# Lighting_Schematic.net
KiCad netlist of a schematic drawn in EAGLE
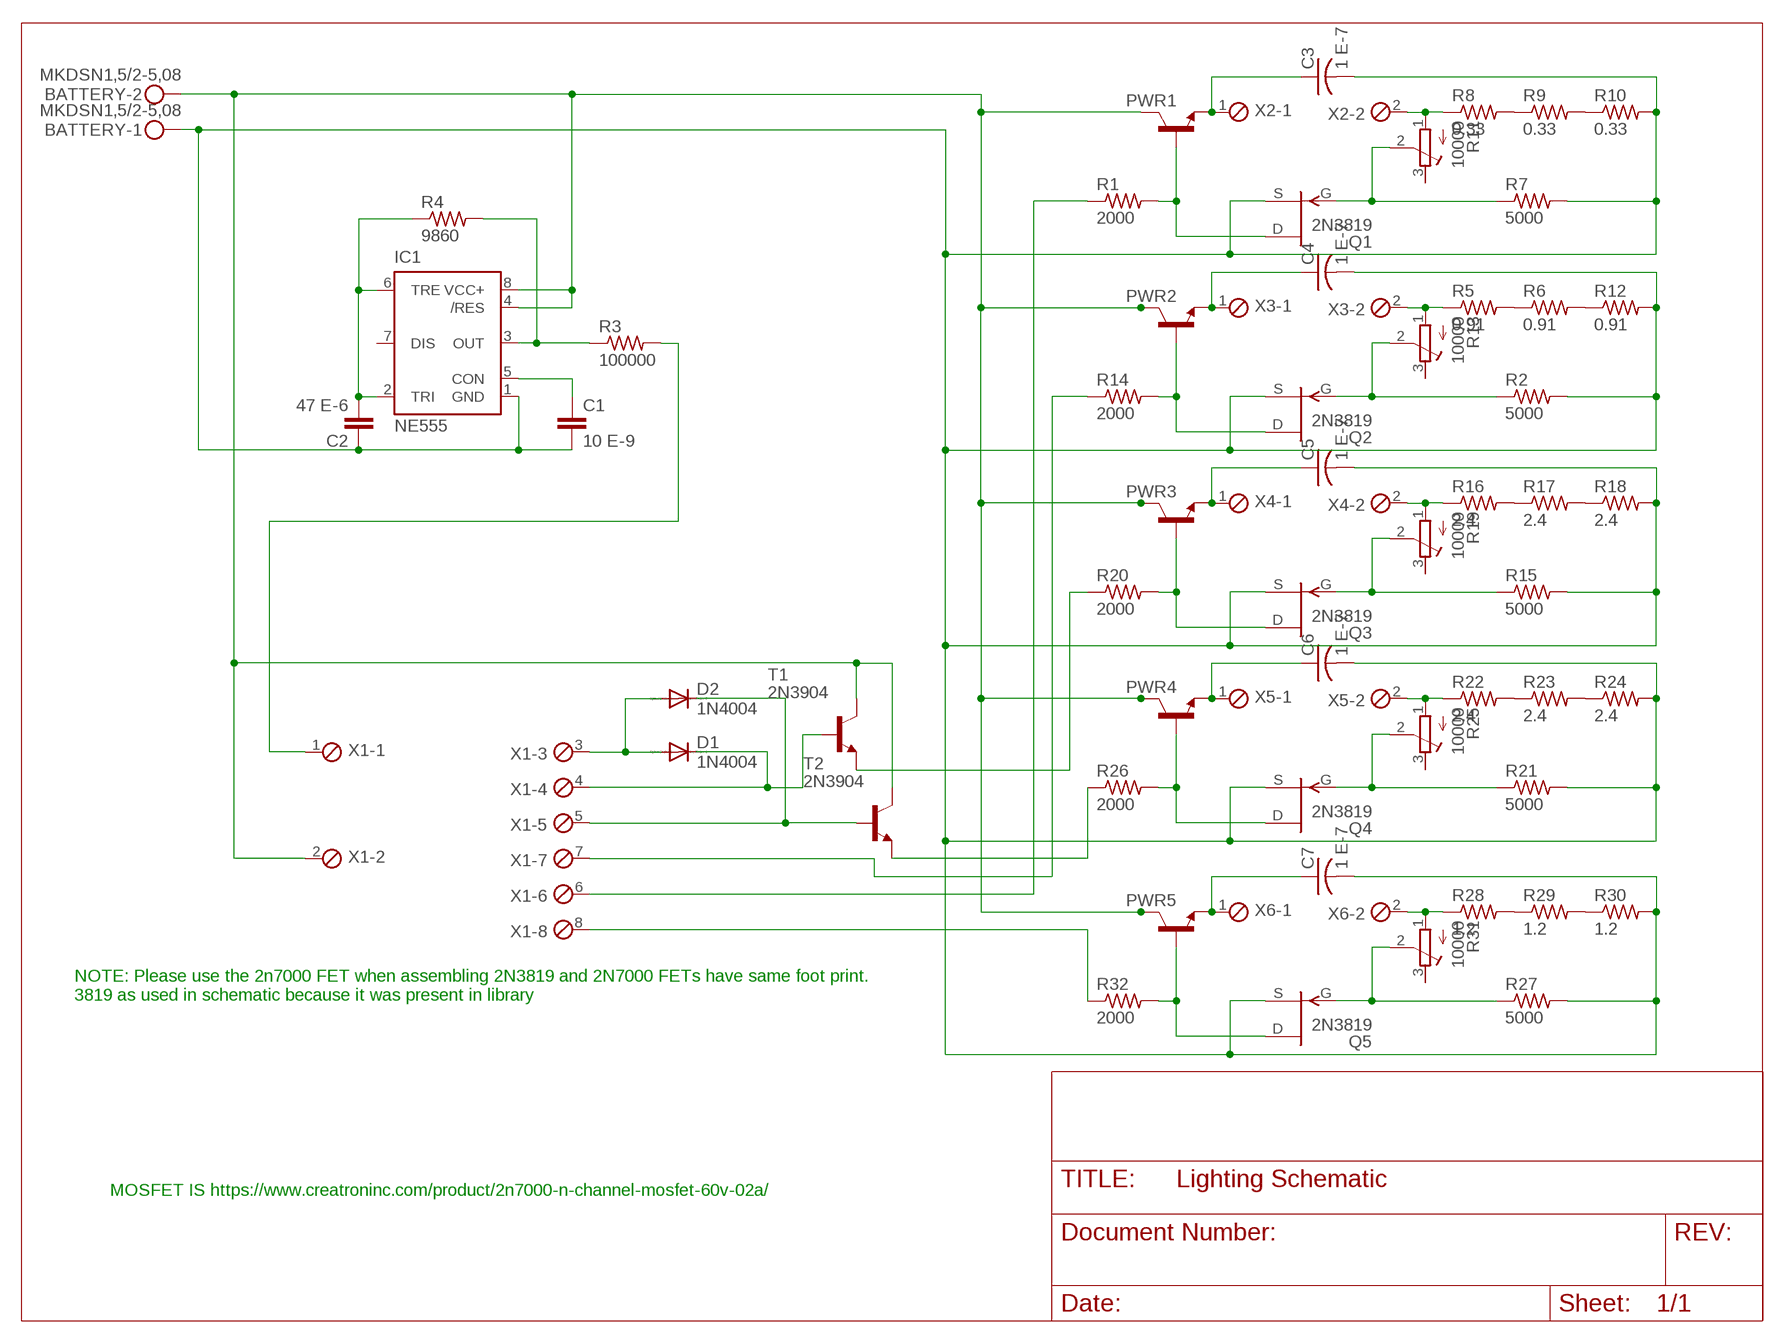
[diagram p0: schematic, sheet 1]

(export (version "E")
  (design (tool "Eeschema 10.0.6"))
  (components
    (comp (ref "BATTERY")
      (value "MKDSN1,5/2-5,08")
      (footprint "eagle-import:MKDSN1,5_2-5,08")
      (libsource (lib "eagle-import") (part "MKDSN1,5/2-5,08"))
    )
    (comp (ref "C1")
      (value "10 E-9")
      (footprint "eagle-import:C2.5-5")
      (libsource (lib "eagle-import") (part "C2.5/5"))
    )
    (comp (ref "C2")
      (value "47 E-6")
      (footprint "eagle-import:C2.5-5")
      (libsource (lib "eagle-import") (part "C2.5/5"))
    )
    (comp (ref "C3")
      (value "1 E-7")
      (footprint "eagle-import:C075-052X106")
      (libsource (lib "eagle-import") (part "C-US075-052X106"))
    )
    (comp (ref "C4")
      (value "1 E-7")
      (footprint "eagle-import:C075-052X106")
      (libsource (lib "eagle-import") (part "C-US075-052X106"))
    )
    (comp (ref "C5")
      (value "1 E-7")
      (footprint "eagle-import:C075-052X106")
      (libsource (lib "eagle-import") (part "C-US075-052X106"))
    )
    (comp (ref "C6")
      (value "1 E-7")
      (footprint "eagle-import:C075-052X106")
      (libsource (lib "eagle-import") (part "C-US075-052X106"))
    )
    (comp (ref "C7")
      (value "1 E-7")
      (footprint "eagle-import:C075-052X106")
      (libsource (lib "eagle-import") (part "C-US075-052X106"))
    )
    (comp (ref "D1")
      (value "1N4004")
      (footprint "eagle-import:DO41-10")
      (libsource (lib "eagle-import") (part "1N4004"))
    )
    (comp (ref "D2")
      (value "1N4004")
      (footprint "eagle-import:DO41-10")
      (libsource (lib "eagle-import") (part "1N4004"))
    )
    (comp (ref "IC1")
      (value "NE555")
      (footprint "eagle-import:DIL-08")
      (fields (field (name "MF") "Arrow Electronics") (field (name "MPN") "NE555N"))
      (libsource (lib "eagle-import") (part "NE555"))
    )
    (comp (ref "PWR1")
      (value "-NPN-TO220V")
      (footprint "eagle-import:TO220V")
      (libsource (lib "eagle-import") (part "-NPN-TO220V"))
    )
    (comp (ref "PWR2")
      (value "-NPN-TO220V")
      (footprint "eagle-import:TO220V")
      (libsource (lib "eagle-import") (part "-NPN-TO220V"))
    )
    (comp (ref "PWR3")
      (value "-NPN-TO220V")
      (footprint "eagle-import:TO220V")
      (libsource (lib "eagle-import") (part "-NPN-TO220V"))
    )
    (comp (ref "PWR4")
      (value "-NPN-TO220V")
      (footprint "eagle-import:TO220V")
      (libsource (lib "eagle-import") (part "-NPN-TO220V"))
    )
    (comp (ref "PWR5")
      (value "-NPN-TO220V")
      (footprint "eagle-import:TO220V")
      (libsource (lib "eagle-import") (part "-NPN-TO220V"))
    )
    (comp (ref "Q1")
      (value "2N3819")
      (footprint "eagle-import:TO92")
      (libsource (lib "eagle-import") (part "2N3819"))
    )
    (comp (ref "Q2")
      (value "2N3819")
      (footprint "eagle-import:TO92")
      (libsource (lib "eagle-import") (part "2N3819"))
    )
    (comp (ref "Q3")
      (value "2N3819")
      (footprint "eagle-import:TO92")
      (libsource (lib "eagle-import") (part "2N3819"))
    )
    (comp (ref "Q4")
      (value "2N3819")
      (footprint "eagle-import:TO92")
      (libsource (lib "eagle-import") (part "2N3819"))
    )
    (comp (ref "Q5")
      (value "2N3819")
      (footprint "eagle-import:TO92")
      (libsource (lib "eagle-import") (part "2N3819"))
    )
    (comp (ref "R1")
      (value "2000")
      (footprint "eagle-import:0207_15")
      (libsource (lib "eagle-import") (part "resistor_348_R-US_0207/15"))
    )
    (comp (ref "R2")
      (value "5000")
      (footprint "eagle-import:0207_10")
      (libsource (lib "eagle-import") (part "R-US_0207/10"))
    )
    (comp (ref "R3")
      (value "100000")
      (footprint "eagle-import:0207_10")
      (libsource (lib "eagle-import") (part "R-US_0207/10"))
    )
    (comp (ref "R4")
      (value "9860")
      (footprint "eagle-import:0207_10")
      (libsource (lib "eagle-import") (part "R-US_0207/10"))
    )
    (comp (ref "R5")
      (value "0.91")
      (footprint "eagle-import:P0817V")
      (libsource (lib "eagle-import") (part "R-US_0817/7V"))
    )
    (comp (ref "R6")
      (value "0.91")
      (footprint "eagle-import:P0817V")
      (libsource (lib "eagle-import") (part "R-US_0817/7V"))
    )
    (comp (ref "R7")
      (value "5000")
      (footprint "eagle-import:0207_10")
      (libsource (lib "eagle-import") (part "R-US_0207/10"))
    )
    (comp (ref "R8")
      (value "0.33")
      (footprint "eagle-import:P0817V")
      (libsource (lib "eagle-import") (part "R-US_0817/7V"))
    )
    (comp (ref "R9")
      (value "0.33")
      (footprint "eagle-import:P0817V")
      (libsource (lib "eagle-import") (part "R-US_0817/7V"))
    )
    (comp (ref "R10")
      (value "0.33")
      (footprint "eagle-import:P0817V")
      (libsource (lib "eagle-import") (part "R-US_0817/7V"))
    )
    (comp (ref "R11")
      (value "10000")
      (footprint "eagle-import:RTRIM3296W")
      (libsource (lib "eagle-import") (part "R-TRIMM3296W"))
    )
    (comp (ref "R12")
      (value "0.91")
      (footprint "eagle-import:P0817V")
      (libsource (lib "eagle-import") (part "R-US_0817/7V"))
    )
    (comp (ref "R13")
      (value "10000")
      (footprint "eagle-import:RTRIM3296W")
      (libsource (lib "eagle-import") (part "R-TRIMM3296W"))
    )
    (comp (ref "R14")
      (value "2000")
      (footprint "eagle-import:0207_15")
      (libsource (lib "eagle-import") (part "resistor_348_R-US_0207/15"))
    )
    (comp (ref "R15")
      (value "5000")
      (footprint "eagle-import:0207_10")
      (libsource (lib "eagle-import") (part "R-US_0207/10"))
    )
    (comp (ref "R16")
      (value "2.4")
      (footprint "eagle-import:P0817V")
      (libsource (lib "eagle-import") (part "R-US_0817/7V"))
    )
    (comp (ref "R17")
      (value "2.4")
      (footprint "eagle-import:P0817V")
      (libsource (lib "eagle-import") (part "R-US_0817/7V"))
    )
    (comp (ref "R18")
      (value "2.4")
      (footprint "eagle-import:P0817V")
      (libsource (lib "eagle-import") (part "R-US_0817/7V"))
    )
    (comp (ref "R19")
      (value "10000")
      (footprint "eagle-import:RTRIM3296W")
      (libsource (lib "eagle-import") (part "R-TRIMM3296W"))
    )
    (comp (ref "R20")
      (value "2000")
      (footprint "eagle-import:0207_15")
      (libsource (lib "eagle-import") (part "resistor_348_R-US_0207/15"))
    )
    (comp (ref "R21")
      (value "5000")
      (footprint "eagle-import:0207_10")
      (libsource (lib "eagle-import") (part "R-US_0207/10"))
    )
    (comp (ref "R22")
      (value "2.4")
      (footprint "eagle-import:P0817V")
      (libsource (lib "eagle-import") (part "R-US_0817/7V"))
    )
    (comp (ref "R23")
      (value "2.4")
      (footprint "eagle-import:P0817V")
      (libsource (lib "eagle-import") (part "R-US_0817/7V"))
    )
    (comp (ref "R24")
      (value "2.4")
      (footprint "eagle-import:P0817V")
      (libsource (lib "eagle-import") (part "R-US_0817/7V"))
    )
    (comp (ref "R25")
      (value "10000")
      (footprint "eagle-import:RTRIM3296W")
      (libsource (lib "eagle-import") (part "R-TRIMM3296W"))
    )
    (comp (ref "R26")
      (value "2000")
      (footprint "eagle-import:0207_15")
      (libsource (lib "eagle-import") (part "resistor_348_R-US_0207/15"))
    )
    (comp (ref "R27")
      (value "5000")
      (footprint "eagle-import:0207_10")
      (libsource (lib "eagle-import") (part "R-US_0207/10"))
    )
    (comp (ref "R28")
      (value "1.2")
      (footprint "eagle-import:P0817V")
      (libsource (lib "eagle-import") (part "R-US_0817/7V"))
    )
    (comp (ref "R29")
      (value "1.2")
      (footprint "eagle-import:P0817V")
      (libsource (lib "eagle-import") (part "R-US_0817/7V"))
    )
    (comp (ref "R30")
      (value "1.2")
      (footprint "eagle-import:P0817V")
      (libsource (lib "eagle-import") (part "R-US_0817/7V"))
    )
    (comp (ref "R31")
      (value "10000")
      (footprint "eagle-import:RTRIM3296W")
      (libsource (lib "eagle-import") (part "R-TRIMM3296W"))
    )
    (comp (ref "R32")
      (value "2000")
      (footprint "eagle-import:0207_15")
      (libsource (lib "eagle-import") (part "resistor_348_R-US_0207/15"))
    )
    (comp (ref "T1")
      (value "2N3904")
      (footprint "eagle-import:TO92")
      (libsource (lib "eagle-import") (part "2N3904"))
    )
    (comp (ref "T2")
      (value "2N3904")
      (footprint "eagle-import:TO92")
      (libsource (lib "eagle-import") (part "2N3904"))
    )
    (comp (ref "X1")
      (value "MPT8")
      (footprint "eagle-import:8POL254")
      (libsource (lib "eagle-import") (part "MPT8"))
    )
    (comp (ref "X2")
      (value "MPT2")
      (footprint "eagle-import:2POL254")
      (libsource (lib "eagle-import") (part "MPT2"))
    )
    (comp (ref "X3")
      (value "MPT2")
      (footprint "eagle-import:2POL254")
      (libsource (lib "eagle-import") (part "MPT2"))
    )
    (comp (ref "X4")
      (value "MPT2")
      (footprint "eagle-import:2POL254")
      (libsource (lib "eagle-import") (part "MPT2"))
    )
    (comp (ref "X5")
      (value "MPT2")
      (footprint "eagle-import:2POL254")
      (libsource (lib "eagle-import") (part "MPT2"))
    )
    (comp (ref "X6")
      (value "MPT2")
      (footprint "eagle-import:2POL254")
      (libsource (lib "eagle-import") (part "MPT2"))
    )
  )
  (nets
    (net (code "1") (name "Net-(BATTERYA-KL)") (class "Default")
      (node (ref "BATTERY") (pin "1") (pinfunction "KL_1") (pintype "passive"))
      (node (ref "C1") (pin "2") (pinfunction "2_2") (pintype "passive"))
      (node (ref "C2") (pin "1") (pinfunction "1_1") (pintype "passive"))
      (node (ref "C3") (pin "2") (pinfunction "2_2") (pintype "passive"))
      (node (ref "C4") (pin "2") (pinfunction "2_2") (pintype "passive"))
      (node (ref "C5") (pin "2") (pinfunction "2_2") (pintype "passive"))
      (node (ref "C6") (pin "2") (pinfunction "2_2") (pintype "passive"))
      (node (ref "C7") (pin "2") (pinfunction "2_2") (pintype "passive"))
      (node (ref "IC1") (pin "1") (pinfunction "GND_1") (pintype "power_in"))
      (node (ref "Q1") (pin "3") (pinfunction "S_3") (pintype "passive"))
      (node (ref "Q2") (pin "3") (pinfunction "S_3") (pintype "passive"))
      (node (ref "Q3") (pin "3") (pinfunction "S_3") (pintype "passive"))
      (node (ref "Q4") (pin "3") (pinfunction "S_3") (pintype "passive"))
      (node (ref "Q5") (pin "3") (pinfunction "S_3") (pintype "passive"))
      (node (ref "R10") (pin "2") (pinfunction "2_2") (pintype "passive"))
      (node (ref "R12") (pin "2") (pinfunction "2_2") (pintype "passive"))
      (node (ref "R15") (pin "2") (pinfunction "2_2") (pintype "passive"))
      (node (ref "R18") (pin "2") (pinfunction "2_2") (pintype "passive"))
      (node (ref "R2") (pin "2") (pinfunction "2_2") (pintype "passive"))
      (node (ref "R21") (pin "2") (pinfunction "2_2") (pintype "passive"))
      (node (ref "R24") (pin "2") (pinfunction "2_2") (pintype "passive"))
      (node (ref "R27") (pin "2") (pinfunction "2_2") (pintype "passive"))
      (node (ref "R30") (pin "2") (pinfunction "2_2") (pintype "passive"))
      (node (ref "R7") (pin "2") (pinfunction "2_2") (pintype "passive"))
    )
    (net (code "2") (name "Net-(BATTERYB-KL)") (class "Default")
      (node (ref "BATTERY") (pin "2") (pinfunction "KL_2") (pintype "passive"))
      (node (ref "IC1") (pin "4") (pinfunction "/RES_4") (pintype "input"))
      (node (ref "IC1") (pin "8") (pinfunction "VCC+_8") (pintype "power_in"))
      (node (ref "PWR1") (pin "2") (pinfunction "C_2") (pintype "passive"))
      (node (ref "PWR2") (pin "2") (pinfunction "C_2") (pintype "passive"))
      (node (ref "PWR3") (pin "2") (pinfunction "C_2") (pintype "passive"))
      (node (ref "PWR4") (pin "2") (pinfunction "C_2") (pintype "passive"))
      (node (ref "PWR5") (pin "2") (pinfunction "C_2") (pintype "passive"))
      (node (ref "T1") (pin "1") (pinfunction "C_1") (pintype "passive"))
      (node (ref "T2") (pin "1") (pinfunction "C_1") (pintype "passive"))
      (node (ref "X1") (pin "2") (pinfunction "1_2") (pintype "passive"))
    )
    (net (code "3") (name "Net-(IC1-CON)") (class "Default")
      (node (ref "C1") (pin "1") (pinfunction "1_1") (pintype "passive"))
      (node (ref "IC1") (pin "5") (pinfunction "CON_5") (pintype "input"))
    )
    (net (code "4") (name "Net-(IC1-OUT)") (class "Default")
      (node (ref "IC1") (pin "3") (pinfunction "OUT_3") (pintype "output"))
      (node (ref "R3") (pin "1") (pinfunction "1_1") (pintype "passive"))
      (node (ref "R4") (pin "2") (pinfunction "2_2") (pintype "passive"))
    )
    (net (code "5") (name "Net-(IC1-TRE)") (class "Default")
      (node (ref "C2") (pin "2") (pinfunction "2_2") (pintype "passive"))
      (node (ref "IC1") (pin "2") (pinfunction "TRI_2") (pintype "input"))
      (node (ref "IC1") (pin "6") (pinfunction "TRE_6") (pintype "input"))
      (node (ref "R4") (pin "1") (pinfunction "1_1") (pintype "passive"))
    )
    (net (code "6") (name "Net-(PWR1-B)") (class "Default")
      (node (ref "PWR1") (pin "1") (pinfunction "B_1") (pintype "passive"))
      (node (ref "Q1") (pin "1") (pinfunction "D_1") (pintype "passive"))
      (node (ref "R1") (pin "2") (pinfunction "2_2") (pintype "passive"))
    )
    (net (code "7") (name "Net-(PWR1-E)") (class "Default")
      (node (ref "C3") (pin "1") (pinfunction "1_1") (pintype "passive"))
      (node (ref "PWR1") (pin "3") (pinfunction "E_3") (pintype "passive"))
      (node (ref "X2") (pin "1") (pinfunction "1_1") (pintype "passive"))
    )
    (net (code "8") (name "Net-(PWR2-B)") (class "Default")
      (node (ref "PWR2") (pin "1") (pinfunction "B_1") (pintype "passive"))
      (node (ref "Q2") (pin "1") (pinfunction "D_1") (pintype "passive"))
      (node (ref "R14") (pin "2") (pinfunction "2_2") (pintype "passive"))
    )
    (net (code "9") (name "Net-(PWR2-E)") (class "Default")
      (node (ref "C4") (pin "1") (pinfunction "1_1") (pintype "passive"))
      (node (ref "PWR2") (pin "3") (pinfunction "E_3") (pintype "passive"))
      (node (ref "X3") (pin "1") (pinfunction "1_1") (pintype "passive"))
    )
    (net (code "10") (name "Net-(PWR3-B)") (class "Default")
      (node (ref "PWR3") (pin "1") (pinfunction "B_1") (pintype "passive"))
      (node (ref "Q3") (pin "1") (pinfunction "D_1") (pintype "passive"))
      (node (ref "R20") (pin "2") (pinfunction "2_2") (pintype "passive"))
    )
    (net (code "11") (name "Net-(PWR3-E)") (class "Default")
      (node (ref "C5") (pin "1") (pinfunction "1_1") (pintype "passive"))
      (node (ref "PWR3") (pin "3") (pinfunction "E_3") (pintype "passive"))
      (node (ref "X4") (pin "1") (pinfunction "1_1") (pintype "passive"))
    )
    (net (code "12") (name "Net-(PWR4-B)") (class "Default")
      (node (ref "PWR4") (pin "1") (pinfunction "B_1") (pintype "passive"))
      (node (ref "Q4") (pin "1") (pinfunction "D_1") (pintype "passive"))
      (node (ref "R26") (pin "2") (pinfunction "2_2") (pintype "passive"))
    )
    (net (code "13") (name "Net-(PWR4-E)") (class "Default")
      (node (ref "C6") (pin "1") (pinfunction "1_1") (pintype "passive"))
      (node (ref "PWR4") (pin "3") (pinfunction "E_3") (pintype "passive"))
      (node (ref "X5") (pin "1") (pinfunction "1_1") (pintype "passive"))
    )
    (net (code "14") (name "Net-(PWR5-B)") (class "Default")
      (node (ref "PWR5") (pin "1") (pinfunction "B_1") (pintype "passive"))
      (node (ref "Q5") (pin "1") (pinfunction "D_1") (pintype "passive"))
      (node (ref "R32") (pin "2") (pinfunction "2_2") (pintype "passive"))
    )
    (net (code "15") (name "Net-(PWR5-E)") (class "Default")
      (node (ref "C7") (pin "1") (pinfunction "1_1") (pintype "passive"))
      (node (ref "PWR5") (pin "3") (pinfunction "E_3") (pintype "passive"))
      (node (ref "X6") (pin "1") (pinfunction "1_1") (pintype "passive"))
    )
    (net (code "16") (name "Net-(Q1-G)") (class "Default")
      (node (ref "Q1") (pin "2") (pinfunction "G_2") (pintype "passive"))
      (node (ref "R11") (pin "2") (pinfunction "S_2") (pintype "passive"))
      (node (ref "R7") (pin "1") (pinfunction "1_1") (pintype "passive"))
    )
    (net (code "17") (name "Net-(Q2-G)") (class "Default")
      (node (ref "Q2") (pin "2") (pinfunction "G_2") (pintype "passive"))
      (node (ref "R13") (pin "2") (pinfunction "S_2") (pintype "passive"))
      (node (ref "R2") (pin "1") (pinfunction "1_1") (pintype "passive"))
    )
    (net (code "18") (name "Net-(Q3-G)") (class "Default")
      (node (ref "Q3") (pin "2") (pinfunction "G_2") (pintype "passive"))
      (node (ref "R15") (pin "1") (pinfunction "1_1") (pintype "passive"))
      (node (ref "R19") (pin "2") (pinfunction "S_2") (pintype "passive"))
    )
    (net (code "19") (name "Net-(Q4-G)") (class "Default")
      (node (ref "Q4") (pin "2") (pinfunction "G_2") (pintype "passive"))
      (node (ref "R21") (pin "1") (pinfunction "1_1") (pintype "passive"))
      (node (ref "R25") (pin "2") (pinfunction "S_2") (pintype "passive"))
    )
    (net (code "20") (name "Net-(Q5-G)") (class "Default")
      (node (ref "Q5") (pin "2") (pinfunction "G_2") (pintype "passive"))
      (node (ref "R27") (pin "1") (pinfunction "1_1") (pintype "passive"))
      (node (ref "R31") (pin "2") (pinfunction "S_2") (pintype "passive"))
    )
    (net (code "21") (name "Net-(R3-Pad2)") (class "Default")
      (node (ref "R3") (pin "2") (pinfunction "2_2") (pintype "passive"))
      (node (ref "X1") (pin "1") (pinfunction "1_1") (pintype "passive"))
    )
    (net (code "22") (name "Net-(R5-Pad2)") (class "Default")
      (node (ref "R5") (pin "2") (pinfunction "2_2") (pintype "passive"))
      (node (ref "R6") (pin "1") (pinfunction "1_1") (pintype "passive"))
    )
    (net (code "23") (name "Net-(R8-Pad2)") (class "Default")
      (node (ref "R8") (pin "2") (pinfunction "2_2") (pintype "passive"))
      (node (ref "R9") (pin "1") (pinfunction "1_1") (pintype "passive"))
    )
    (net (code "24") (name "Net-(R10-Pad1)") (class "Default")
      (node (ref "R10") (pin "1") (pinfunction "1_1") (pintype "passive"))
      (node (ref "R9") (pin "2") (pinfunction "2_2") (pintype "passive"))
    )
    (net (code "25") (name "Net-(R11-A)") (class "Default")
      (node (ref "R11") (pin "1") (pinfunction "A_1") (pintype "passive"))
      (node (ref "R8") (pin "1") (pinfunction "1_1") (pintype "passive"))
      (node (ref "X2") (pin "2") (pinfunction "1_2") (pintype "passive"))
    )
    (net (code "26") (name "Net-(R12-Pad1)") (class "Default")
      (node (ref "R12") (pin "1") (pinfunction "1_1") (pintype "passive"))
      (node (ref "R6") (pin "2") (pinfunction "2_2") (pintype "passive"))
    )
    (net (code "27") (name "Net-(R13-A)") (class "Default")
      (node (ref "R13") (pin "1") (pinfunction "A_1") (pintype "passive"))
      (node (ref "R5") (pin "1") (pinfunction "1_1") (pintype "passive"))
      (node (ref "X3") (pin "2") (pinfunction "1_2") (pintype "passive"))
    )
    (net (code "28") (name "Net-(R16-Pad2)") (class "Default")
      (node (ref "R16") (pin "2") (pinfunction "2_2") (pintype "passive"))
      (node (ref "R17") (pin "1") (pinfunction "1_1") (pintype "passive"))
    )
    (net (code "29") (name "Net-(R17-Pad2)") (class "Default")
      (node (ref "R17") (pin "2") (pinfunction "2_2") (pintype "passive"))
      (node (ref "R18") (pin "1") (pinfunction "1_1") (pintype "passive"))
    )
    (net (code "30") (name "Net-(R19-A)") (class "Default")
      (node (ref "R16") (pin "1") (pinfunction "1_1") (pintype "passive"))
      (node (ref "R19") (pin "1") (pinfunction "A_1") (pintype "passive"))
      (node (ref "X4") (pin "2") (pinfunction "1_2") (pintype "passive"))
    )
    (net (code "31") (name "Net-(R22-Pad2)") (class "Default")
      (node (ref "R22") (pin "2") (pinfunction "2_2") (pintype "passive"))
      (node (ref "R23") (pin "1") (pinfunction "1_1") (pintype "passive"))
    )
    (net (code "32") (name "Net-(R23-Pad2)") (class "Default")
      (node (ref "R23") (pin "2") (pinfunction "2_2") (pintype "passive"))
      (node (ref "R24") (pin "1") (pinfunction "1_1") (pintype "passive"))
    )
    (net (code "33") (name "Net-(R25-A)") (class "Default")
      (node (ref "R22") (pin "1") (pinfunction "1_1") (pintype "passive"))
      (node (ref "R25") (pin "1") (pinfunction "A_1") (pintype "passive"))
      (node (ref "X5") (pin "2") (pinfunction "1_2") (pintype "passive"))
    )
    (net (code "34") (name "Net-(R28-Pad2)") (class "Default")
      (node (ref "R28") (pin "2") (pinfunction "2_2") (pintype "passive"))
      (node (ref "R29") (pin "1") (pinfunction "1_1") (pintype "passive"))
    )
    (net (code "35") (name "Net-(R29-Pad2)") (class "Default")
      (node (ref "R29") (pin "2") (pinfunction "2_2") (pintype "passive"))
      (node (ref "R30") (pin "1") (pinfunction "1_1") (pintype "passive"))
    )
    (net (code "36") (name "Net-(R31-A)") (class "Default")
      (node (ref "R28") (pin "1") (pinfunction "1_1") (pintype "passive"))
      (node (ref "R31") (pin "1") (pinfunction "A_1") (pintype "passive"))
      (node (ref "X6") (pin "2") (pinfunction "1_2") (pintype "passive"))
    )
    (net (code "37") (name "Net-(T1-B)") (class "Default")
      (node (ref "D1") (pin "C") (pinfunction "C_C") (pintype "passive"))
      (node (ref "T1") (pin "2") (pinfunction "B_2") (pintype "passive"))
      (node (ref "X1") (pin "4") (pinfunction "1_4") (pintype "passive"))
    )
    (net (code "38") (name "Net-(T1-E)") (class "Default")
      (node (ref "R20") (pin "1") (pinfunction "1_1") (pintype "passive"))
      (node (ref "T1") (pin "3") (pinfunction "E_3") (pintype "passive"))
    )
    (net (code "39") (name "Net-(T2-B)") (class "Default")
      (node (ref "D2") (pin "C") (pinfunction "C_C") (pintype "passive"))
      (node (ref "T2") (pin "2") (pinfunction "B_2") (pintype "passive"))
      (node (ref "X1") (pin "5") (pinfunction "1_5") (pintype "passive"))
    )
    (net (code "40") (name "Net-(T2-E)") (class "Default")
      (node (ref "R26") (pin "1") (pinfunction "1_1") (pintype "passive"))
      (node (ref "T2") (pin "3") (pinfunction "E_3") (pintype "passive"))
    )
    (net (code "41") (name "Net-(X1C-1)") (class "Default")
      (node (ref "D1") (pin "A") (pinfunction "A_A") (pintype "passive"))
      (node (ref "D2") (pin "A") (pinfunction "A_A") (pintype "passive"))
      (node (ref "X1") (pin "3") (pinfunction "1_3") (pintype "passive"))
    )
    (net (code "42") (name "Net-(X1F-1)") (class "Default")
      (node (ref "R1") (pin "1") (pinfunction "1_1") (pintype "passive"))
      (node (ref "X1") (pin "6") (pinfunction "1_6") (pintype "passive"))
    )
    (net (code "43") (name "Net-(X1G-1)") (class "Default")
      (node (ref "R14") (pin "1") (pinfunction "1_1") (pintype "passive"))
      (node (ref "X1") (pin "7") (pinfunction "1_7") (pintype "passive"))
    )
    (net (code "44") (name "Net-(X1H-1)") (class "Default")
      (node (ref "R32") (pin "1") (pinfunction "1_1") (pintype "passive"))
      (node (ref "X1") (pin "8") (pinfunction "1_8") (pintype "passive"))
    )
    (net (code "45") (name "unconnected-(IC1-DIS-Pad7)") (class "Default")
      (node (ref "IC1") (pin "7") (pinfunction "DIS_7") (pintype "input"))
    )
    (net (code "46") (name "unconnected-(R11-E-Pad3)") (class "Default")
      (node (ref "R11") (pin "3") (pinfunction "E_3") (pintype "passive"))
    )
    (net (code "47") (name "unconnected-(R13-E-Pad3)") (class "Default")
      (node (ref "R13") (pin "3") (pinfunction "E_3") (pintype "passive"))
    )
    (net (code "48") (name "unconnected-(R19-E-Pad3)") (class "Default")
      (node (ref "R19") (pin "3") (pinfunction "E_3") (pintype "passive"))
    )
    (net (code "49") (name "unconnected-(R25-E-Pad3)") (class "Default")
      (node (ref "R25") (pin "3") (pinfunction "E_3") (pintype "passive"))
    )
    (net (code "50") (name "unconnected-(R31-E-Pad3)") (class "Default")
      (node (ref "R31") (pin "3") (pinfunction "E_3") (pintype "passive"))
    )
  )
)
